# Schematic.net
KiCad netlist of a schematic drawn in Altium Designer
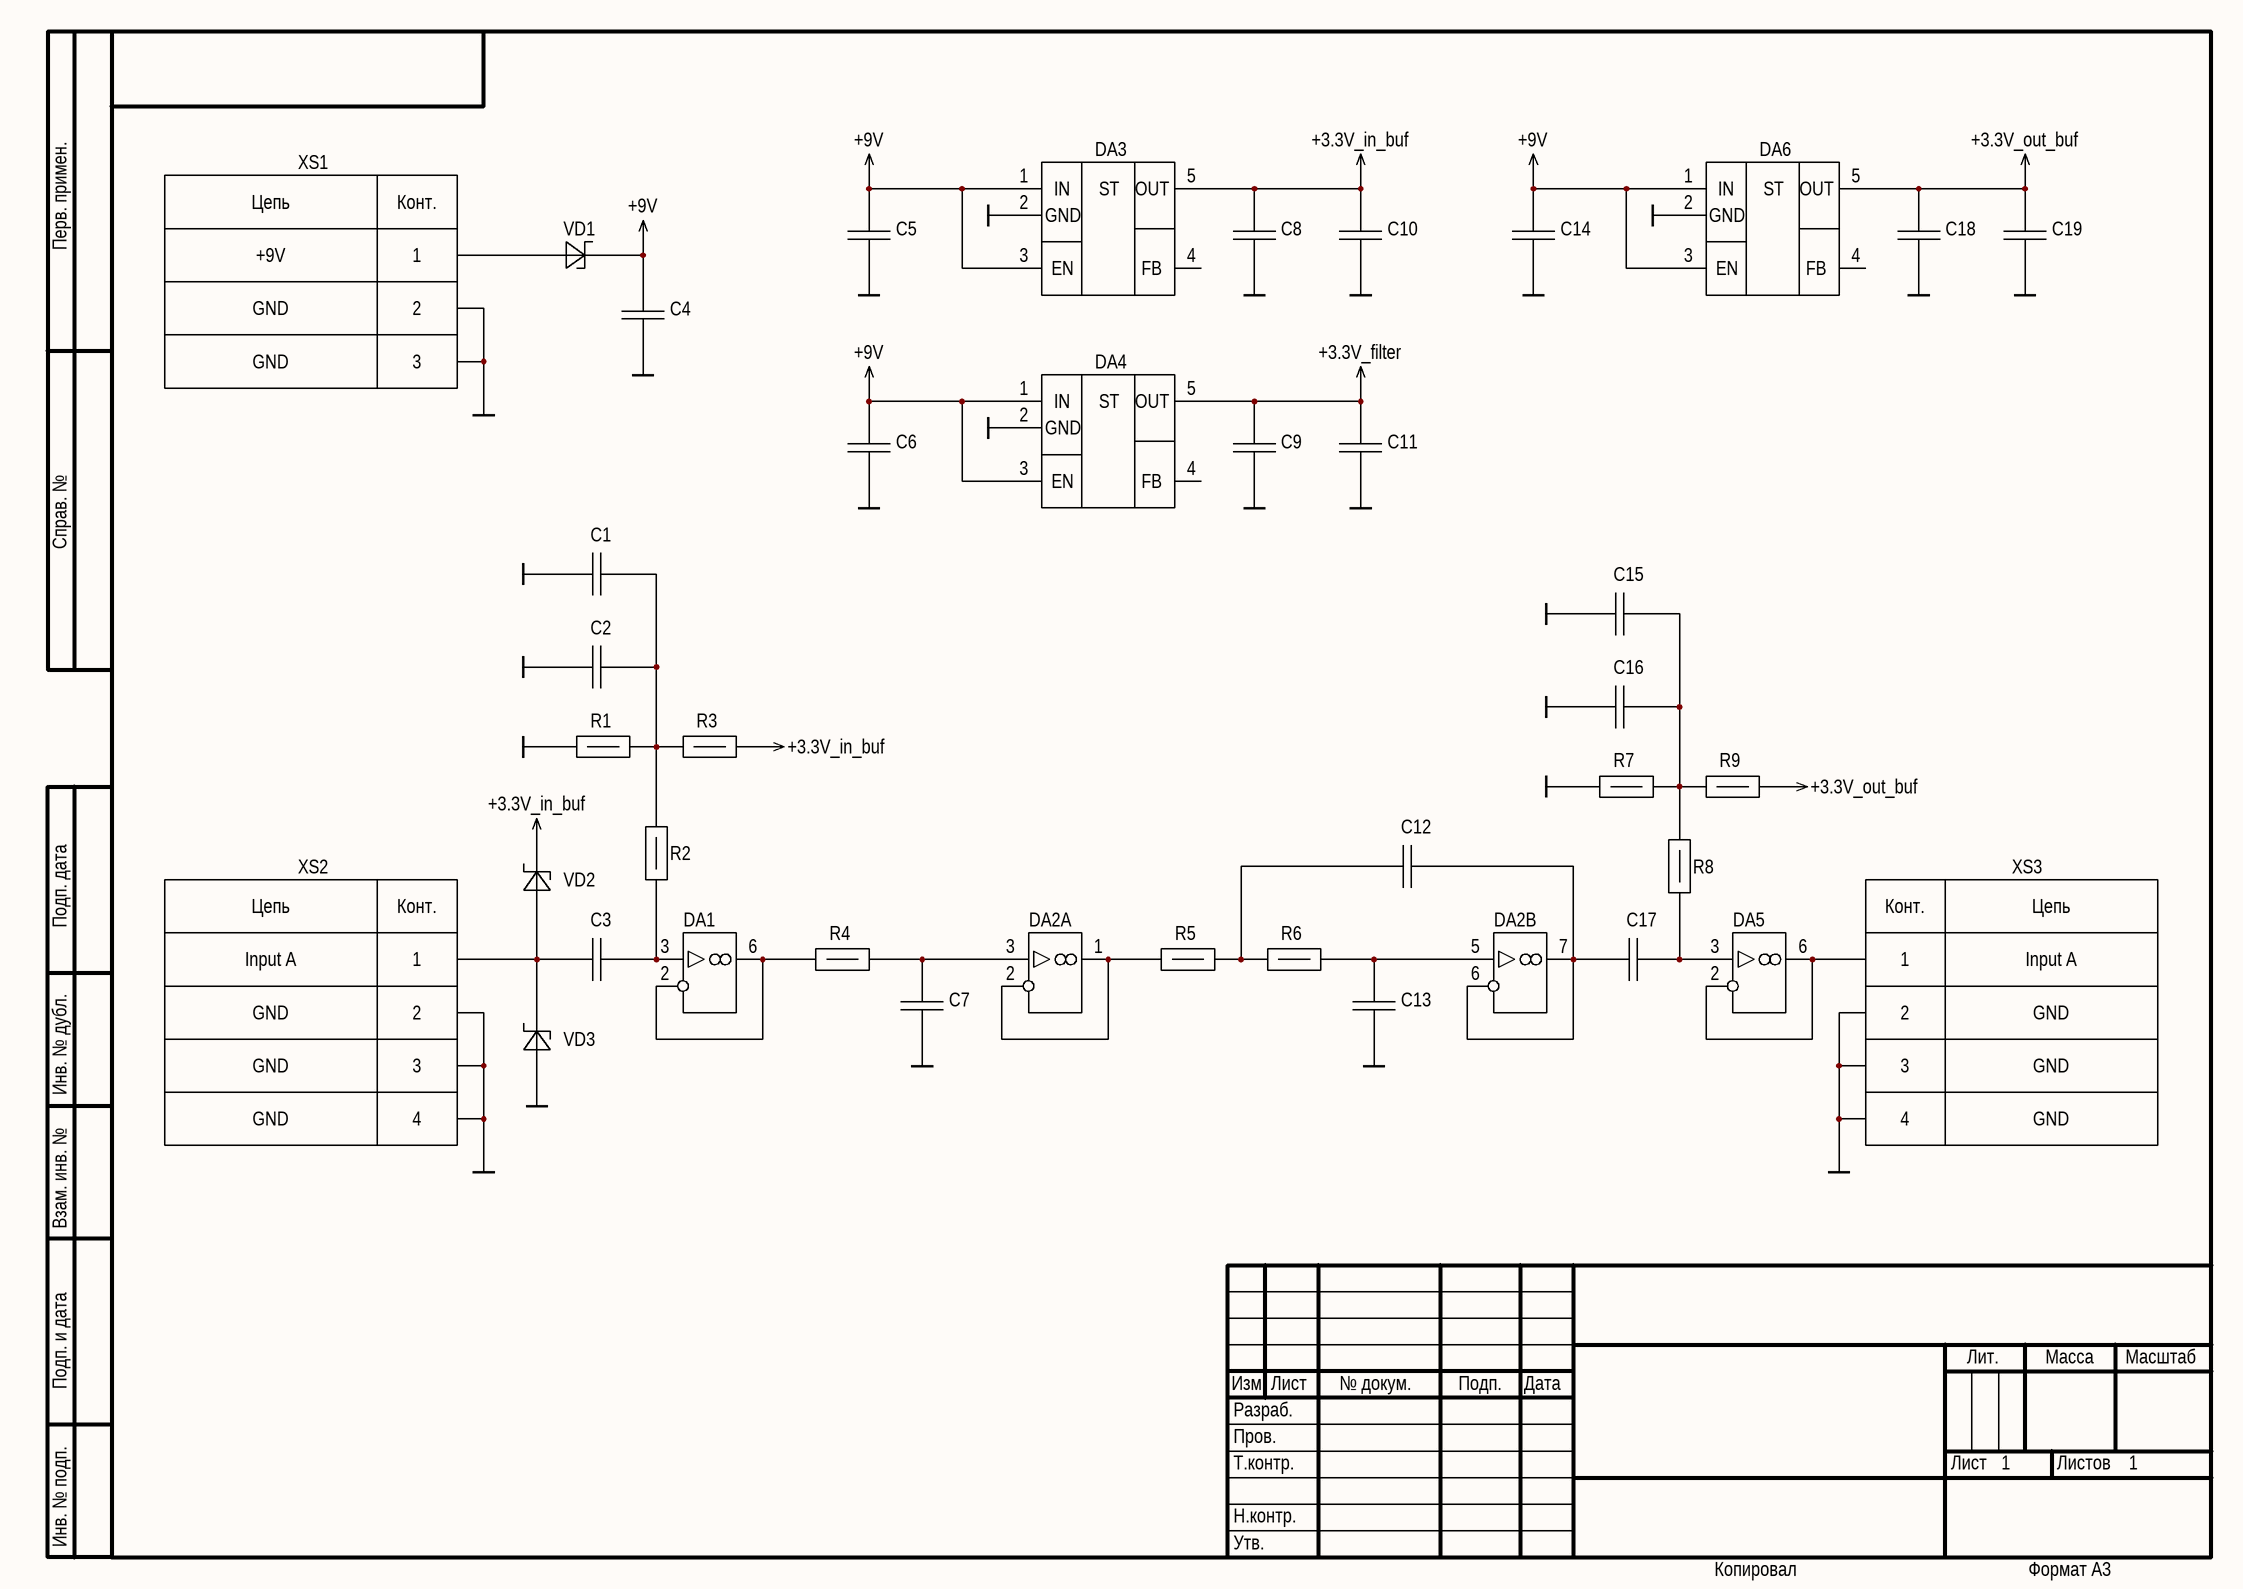
[diagram p0: Schematic.SchDoc]

(export (version "E")
  (design (tool "Eeschema 10.0.6"))
  (components
    (comp (ref "C1")
      (value "10 uF x 10 V")
      (footprint "CAPC2012X06N")
      (description "MLCC - Multilayer Ceramic Capacitors")
      (fields (field (name "TOLERANCE") "10%"))
      (libsource (lib "RLC") (part "KGM21AR71A106KU"))
    )
    (comp (ref "C2")
      (value "0.1 uF x 100 V")
      (footprint "CAPC2012X06N")
      (description "MLCC - Multilayer Ceramic Capacitors")
      (fields (field (name "TOLERANCE") "10%"))
      (libsource (lib "RLC") (part "C2012X7R2A104K125AE"))
    )
    (comp (ref "C3")
      (value "0.1 uF x 100 V")
      (footprint "CAPC2012X06N")
      (description "MLCC - Multilayer Ceramic Capacitors")
      (fields (field (name "TOLERANCE") "10%"))
      (libsource (lib "RLC") (part "C2012X7R2A104K125AE"))
    )
    (comp (ref "C4")
      (value "10 uF x 10 V")
      (footprint "CAPC2012X06N")
      (description "MLCC - Multilayer Ceramic Capacitors")
      (fields (field (name "TOLERANCE") "10%"))
      (libsource (lib "RLC") (part "KGM21AR71A106KU"))
    )
    (comp (ref "C5")
      (value "10 uF x 10 V")
      (footprint "CAPC2012X06N")
      (description "MLCC - Multilayer Ceramic Capacitors")
      (fields (field (name "TOLERANCE") "10%"))
      (libsource (lib "RLC") (part "KGM21AR71A106KU"))
    )
    (comp (ref "C6")
      (value "10 uF x 10 V")
      (footprint "CAPC2012X06N")
      (description "MLCC - Multilayer Ceramic Capacitors")
      (fields (field (name "TOLERANCE") "10%"))
      (libsource (lib "RLC") (part "KGM21AR71A106KU"))
    )
    (comp (ref "C7")
      (value "1 nF x 450 V")
      (footprint "CAPC2012X06N")
      (description "MLCC - Multilayer Ceramic Capacitors")
      (fields (field (name "TOLERANCE") "5%"))
      (libsource (lib "RLC") (part "C2012NP02W102J060AA"))
    )
    (comp (ref "C8")
      (value "0.1 uF x 100 V")
      (footprint "CAPC2012X06N")
      (description "MLCC - Multilayer Ceramic Capacitors")
      (fields (field (name "TOLERANCE") "10%"))
      (libsource (lib "RLC") (part "C2012X7R2A104K125AE"))
    )
    (comp (ref "C9")
      (value "0.1 uF x 100 V")
      (footprint "CAPC2012X06N")
      (description "MLCC - Multilayer Ceramic Capacitors")
      (fields (field (name "TOLERANCE") "10%"))
      (libsource (lib "RLC") (part "C2012X7R2A104K125AE"))
    )
    (comp (ref "C10")
      (value "10 uF x 10 V")
      (footprint "CAPC2012X06N")
      (description "MLCC - Multilayer Ceramic Capacitors")
      (fields (field (name "TOLERANCE") "10%"))
      (libsource (lib "RLC") (part "KGM21AR71A106KU"))
    )
    (comp (ref "C11")
      (value "10 uF x 10 V")
      (footprint "CAPC2012X06N")
      (description "MLCC - Multilayer Ceramic Capacitors")
      (fields (field (name "TOLERANCE") "10%"))
      (libsource (lib "RLC") (part "KGM21AR71A106KU"))
    )
    (comp (ref "C12")
      (value "2 nF x 25 V")
      (footprint "CAPC2012X06N")
      (description "MLCC - Multilayer Ceramic Capacitors")
      (fields (field (name "TOLERANCE") "5%"))
      (libsource (lib "RLC") (part "08053A202JAT2A"))
    )
    (comp (ref "C13")
      (value "1 nF x 450 V")
      (footprint "CAPC2012X06N")
      (description "MLCC - Multilayer Ceramic Capacitors")
      (fields (field (name "TOLERANCE") "5%"))
      (libsource (lib "RLC") (part "C2012NP02W102J060AA"))
    )
    (comp (ref "C14")
      (value "10 uF x 10 V")
      (footprint "CAPC2012X06N")
      (description "MLCC - Multilayer Ceramic Capacitors")
      (fields (field (name "TOLERANCE") "10%"))
      (libsource (lib "RLC") (part "KGM21AR71A106KU"))
    )
    (comp (ref "C15")
      (value "10 uF x 10 V")
      (footprint "CAPC2012X06N")
      (description "MLCC - Multilayer Ceramic Capacitors")
      (fields (field (name "TOLERANCE") "10%"))
      (libsource (lib "RLC") (part "KGM21AR71A106KU"))
    )
    (comp (ref "C16")
      (value "0.1 uF x 100 V")
      (footprint "CAPC2012X06N")
      (description "MLCC - Multilayer Ceramic Capacitors")
      (fields (field (name "TOLERANCE") "10%"))
      (libsource (lib "RLC") (part "C2012X7R2A104K125AE"))
    )
    (comp (ref "C17")
      (value "0.1 uF x 100 V")
      (footprint "CAPC2012X06N")
      (description "MLCC - Multilayer Ceramic Capacitors")
      (fields (field (name "TOLERANCE") "10%"))
      (libsource (lib "RLC") (part "C2012X7R2A104K125AE"))
    )
    (comp (ref "C18")
      (value "0.1 uF x 100 V")
      (footprint "CAPC2012X06N")
      (description "MLCC - Multilayer Ceramic Capacitors")
      (fields (field (name "TOLERANCE") "10%"))
      (libsource (lib "RLC") (part "C2012X7R2A104K125AE"))
    )
    (comp (ref "C19")
      (value "10 uF x 10 V")
      (footprint "CAPC2012X06N")
      (description "MLCC - Multilayer Ceramic Capacitors")
      (fields (field (name "TOLERANCE") "10%"))
      (libsource (lib "RLC") (part "KGM21AR71A106KU"))
    )
    (comp (ref "DA1")
      (value "OPA735AID")
      (footprint "D0008A")
      (description "0.05µV/°C max, SINGLE-SUPPLY CMOS OPERATIONAL AMPLIFIERS Zer∅-Drift Series")
      (libsource (lib "OPAx73x") (part "OPA735AID"))
    )
    (comp (ref "DA2")
      (value "OPA2735AIDGKR")
      (footprint "DGK0008A")
      (description "0.05µV/°C max, SINGLE-SUPPLY CMOS OPERATIONAL AMPLIFIERS Zer∅-Drift Series")
      (libsource (lib "OPAx73x") (part "OPA2735AIDGKR"))
    )
    (comp (ref "DA3")
      (value "TPS76333DBVT")
      (footprint "DBV0005A")
      (description "150mA, 10V, Low-Dropout Voltage Regulator")
      (libsource (lib "TPS763") (part "TPS76333DBVT"))
    )
    (comp (ref "DA4")
      (value "TPS76333DBVT")
      (footprint "DBV0005A")
      (description "150mA, 10V, Low-Dropout Voltage Regulator")
      (libsource (lib "TPS763") (part "TPS76333DBVT"))
    )
    (comp (ref "DA5")
      (value "OPA735AID")
      (footprint "D0008A")
      (description "0.05µV/°C max, SINGLE-SUPPLY CMOS OPERATIONAL AMPLIFIERS Zer∅-Drift Series")
      (libsource (lib "OPAx73x") (part "OPA735AID"))
    )
    (comp (ref "DA6")
      (value "TPS76333DBVT")
      (footprint "DBV0005A")
      (description "150mA, 10V, Low-Dropout Voltage Regulator")
      (libsource (lib "TPS763") (part "TPS76333DBVT"))
    )
    (comp (ref "R1")
      (value "100 kOhms")
      (footprint "RESC2012X06N")
      (description "Thick Film Chip Resistors")
      (fields (field (name "TOLERANCE") "5%"))
      (libsource (lib "RLC") (part "ERJ-HP6J104V"))
    )
    (comp (ref "R2")
      (value "100 kOhms")
      (footprint "RESC2012X06N")
      (description "Thick Film Chip Resistors")
      (fields (field (name "TOLERANCE") "5%"))
      (libsource (lib "RLC") (part "ERJ-HP6J104V"))
    )
    (comp (ref "R3")
      (value "100 kOhms")
      (footprint "RESC2012X06N")
      (description "Thick Film Chip Resistors")
      (fields (field (name "TOLERANCE") "5%"))
      (libsource (lib "RLC") (part "ERJ-HP6J104V"))
    )
    (comp (ref "R4")
      (value "8.06 kOhms")
      (footprint "RESC2012X06N")
      (description "Thick Film Chip Resistors")
      (fields (field (name "TOLERANCE") "1%"))
      (libsource (lib "RLC") (part "ERJ-P06F8061V"))
    )
    (comp (ref "R5")
      (value "4.42 kOhms")
      (footprint "RESC2012X06N")
      (description "Thick Film Chip Resistors")
      (fields (field (name "TOLERANCE") "0.5%"))
      (libsource (lib "RLC") (part "ERJ-6RBD4421V"))
    )
    (comp (ref "R6")
      (value "6.19 kOhms")
      (footprint "RESC2012X06N")
      (description "Thick Film Chip Resistors")
      (fields (field (name "TOLERANCE") "1%"))
      (libsource (lib "RLC") (part "ERJ-HP6F6191V"))
    )
    (comp (ref "R7")
      (value "100 kOhms")
      (footprint "RESC2012X06N")
      (description "Thick Film Chip Resistors")
      (fields (field (name "TOLERANCE") "5%"))
      (libsource (lib "RLC") (part "ERJ-HP6J104V"))
    )
    (comp (ref "R8")
      (value "100 kOhms")
      (footprint "RESC2012X06N")
      (description "Thick Film Chip Resistors")
      (fields (field (name "TOLERANCE") "5%"))
      (libsource (lib "RLC") (part "ERJ-HP6J104V"))
    )
    (comp (ref "R9")
      (value "100 kOhms")
      (footprint "RESC2012X06N")
      (description "Thick Film Chip Resistors")
      (fields (field (name "TOLERANCE") "5%"))
      (libsource (lib "RLC") (part "ERJ-HP6J104V"))
    )
    (comp (ref "VD1")
      (value "BAT54W-HG3-18")
      (footprint "SOD-123")
      (description "Schottky Diodes & Rectifiers 30V Schottky DIODE")
      (libsource (lib "BAT54W-HG3-18") (part "BAT54W-HG3-18"))
    )
    (comp (ref "VD2")
      (value "BAT54W-HG3-18")
      (footprint "SOD-123")
      (description "Schottky Diodes & Rectifiers 30V Schottky DIODE")
      (libsource (lib "BAT54W-HG3-18") (part "BAT54W-HG3-18"))
    )
    (comp (ref "VD3")
      (value "BAT54W-HG3-18")
      (footprint "SOD-123")
      (description "Schottky Diodes & Rectifiers 30V Schottky DIODE")
      (libsource (lib "BAT54W-HG3-18") (part "BAT54W-HG3-18"))
    )
    (comp (ref "XS1")
      (value "PJ-002AH")
      (footprint "PJ-002AH (Same Sky)")
      (description "DC POWER JACK")
      (libsource (lib "PJ-002AH") (part "PJ-002AH"))
    )
    (comp (ref "XS2")
      (value "0731385003")
      (footprint "0731385003 (Molex)")
      (description "BNC Connector Jack")
      (libsource (lib "0731385003") (part "0731385003"))
    )
    (comp (ref "XS3")
      (value "0731385003")
      (footprint "0731385003 (Molex)")
      (description "BNC Connector Jack")
      (libsource (lib "0731385003") (part "0731385003"))
    )
  )
  (nets
    (net (code "1") (name "+3.3V_filter") (class "Default")
      (node (ref "C11") (pin "1") (pinfunction "1_1") (pintype "passive"))
      (node (ref "C9") (pin "1") (pinfunction "1_1") (pintype "passive"))
      (node (ref "DA4") (pin "5") (pinfunction "OUT_5") (pintype "passive"))
    )
    (net (code "2") (name "+3.3V_in_buf") (class "Default")
      (node (ref "C10") (pin "1") (pinfunction "1_1") (pintype "passive"))
      (node (ref "C8") (pin "1") (pinfunction "1_1") (pintype "passive"))
      (node (ref "DA3") (pin "5") (pinfunction "OUT_5") (pintype "passive"))
      (node (ref "R3") (pin "1") (pinfunction "1_1") (pintype "passive"))
      (node (ref "VD2") (pin "1") (pinfunction "1_1") (pintype "passive"))
    )
    (net (code "3") (name "+3.3V_out_buf") (class "Default")
      (node (ref "C18") (pin "1") (pinfunction "1_1") (pintype "passive"))
      (node (ref "C19") (pin "1") (pinfunction "1_1") (pintype "passive"))
      (node (ref "DA6") (pin "5") (pinfunction "OUT_5") (pintype "passive"))
      (node (ref "R9") (pin "1") (pinfunction "1_1") (pintype "passive"))
    )
    (net (code "4") (name "+9V") (class "Default")
      (node (ref "C14") (pin "1") (pinfunction "1_1") (pintype "passive"))
      (node (ref "C4") (pin "1") (pinfunction "1_1") (pintype "passive"))
      (node (ref "C5") (pin "1") (pinfunction "1_1") (pintype "passive"))
      (node (ref "C6") (pin "1") (pinfunction "1_1") (pintype "passive"))
      (node (ref "DA3") (pin "1") (pinfunction "IN_1") (pintype "passive"))
      (node (ref "DA3") (pin "3") (pinfunction "EN_3") (pintype "passive"))
      (node (ref "DA4") (pin "1") (pinfunction "IN_1") (pintype "passive"))
      (node (ref "DA4") (pin "3") (pinfunction "EN_3") (pintype "passive"))
      (node (ref "DA6") (pin "1") (pinfunction "IN_1") (pintype "passive"))
      (node (ref "DA6") (pin "3") (pinfunction "EN_3") (pintype "passive"))
      (node (ref "VD1") (pin "1") (pinfunction "1_1") (pintype "passive"))
    )
    (net (code "5") (name "GND") (class "Default")
      (node (ref "C1") (pin "1") (pinfunction "1_1") (pintype "passive"))
      (node (ref "C10") (pin "2") (pinfunction "2_2") (pintype "passive"))
      (node (ref "C11") (pin "2") (pinfunction "2_2") (pintype "passive"))
      (node (ref "C13") (pin "2") (pinfunction "2_2") (pintype "passive"))
      (node (ref "C14") (pin "2") (pinfunction "2_2") (pintype "passive"))
      (node (ref "C15") (pin "1") (pinfunction "1_1") (pintype "passive"))
      (node (ref "C16") (pin "2") (pinfunction "2_2") (pintype "passive"))
      (node (ref "C18") (pin "2") (pinfunction "2_2") (pintype "passive"))
      (node (ref "C19") (pin "2") (pinfunction "2_2") (pintype "passive"))
      (node (ref "C2") (pin "2") (pinfunction "2_2") (pintype "passive"))
      (node (ref "C4") (pin "2") (pinfunction "2_2") (pintype "passive"))
      (node (ref "C5") (pin "2") (pinfunction "2_2") (pintype "passive"))
      (node (ref "C6") (pin "2") (pinfunction "2_2") (pintype "passive"))
      (node (ref "C7") (pin "2") (pinfunction "2_2") (pintype "passive"))
      (node (ref "C8") (pin "2") (pinfunction "2_2") (pintype "passive"))
      (node (ref "C9") (pin "2") (pinfunction "2_2") (pintype "passive"))
      (node (ref "DA3") (pin "2") (pinfunction "GND_2") (pintype "passive"))
      (node (ref "DA4") (pin "2") (pinfunction "GND_2") (pintype "passive"))
      (node (ref "DA6") (pin "2") (pinfunction "GND_2") (pintype "passive"))
      (node (ref "R1") (pin "2") (pinfunction "2_2") (pintype "passive"))
      (node (ref "R7") (pin "2") (pinfunction "2_2") (pintype "passive"))
      (node (ref "VD3") (pin "2") (pinfunction "2_2") (pintype "passive"))
      (node (ref "XS1") (pin "2") (pinfunction "GND_2") (pintype "passive"))
      (node (ref "XS1") (pin "3") (pinfunction "GND_3") (pintype "passive"))
      (node (ref "XS2") (pin "2") (pinfunction "GND_2") (pintype "passive"))
      (node (ref "XS2") (pin "3") (pinfunction "GND_3") (pintype "passive"))
      (node (ref "XS2") (pin "4") (pinfunction "GND_4") (pintype "passive"))
      (node (ref "XS3") (pin "2") (pinfunction "GND_2") (pintype "passive"))
      (node (ref "XS3") (pin "3") (pinfunction "GND_3") (pintype "passive"))
      (node (ref "XS3") (pin "4") (pinfunction "GND_4") (pintype "passive"))
    )
    (net (code "6") (name "Net-(C1-Pad2)") (class "Default")
      (node (ref "C1") (pin "2") (pinfunction "2_2") (pintype "passive"))
      (node (ref "C2") (pin "1") (pinfunction "1_1") (pintype "passive"))
      (node (ref "R1") (pin "1") (pinfunction "1_1") (pintype "passive"))
      (node (ref "R2") (pin "2") (pinfunction "2_2") (pintype "passive"))
      (node (ref "R3") (pin "2") (pinfunction "2_2") (pintype "passive"))
    )
    (net (code "7") (name "Net-(C12-Pad1)") (class "Default")
      (node (ref "C12") (pin "1") (pinfunction "1_1") (pintype "passive"))
      (node (ref "R5") (pin "2") (pinfunction "2_2") (pintype "passive"))
      (node (ref "R6") (pin "1") (pinfunction "1_1") (pintype "passive"))
    )
    (net (code "8") (name "Net-(C15-Pad2)") (class "Default")
      (node (ref "C15") (pin "2") (pinfunction "2_2") (pintype "passive"))
      (node (ref "C16") (pin "1") (pinfunction "1_1") (pintype "passive"))
      (node (ref "R7") (pin "1") (pinfunction "1_1") (pintype "passive"))
      (node (ref "R8") (pin "2") (pinfunction "2_2") (pintype "passive"))
      (node (ref "R9") (pin "2") (pinfunction "2_2") (pintype "passive"))
    )
    (net (code "9") (name "Net-(DA1-+IN)") (class "Default")
      (node (ref "C3") (pin "1") (pinfunction "1_1") (pintype "passive"))
      (node (ref "DA1") (pin "3") (pinfunction "+IN_3") (pintype "passive"))
      (node (ref "R2") (pin "1") (pinfunction "1_1") (pintype "passive"))
    )
    (net (code "10") (name "Net-(DA1--IN)") (class "Default")
      (node (ref "DA1") (pin "2") (pinfunction "-IN_2") (pintype "passive"))
      (node (ref "DA1") (pin "6") (pinfunction "OUT_6") (pintype "passive"))
      (node (ref "R4") (pin "1") (pinfunction "1_1") (pintype "passive"))
    )
    (net (code "11") (name "Net-(DA2A-+IN_A)") (class "Default")
      (node (ref "C7") (pin "1") (pinfunction "1_1") (pintype "passive"))
      (node (ref "DA2") (pin "3") (pinfunction "+IN_A_3") (pintype "passive"))
      (node (ref "R4") (pin "2") (pinfunction "2_2") (pintype "passive"))
    )
    (net (code "12") (name "Net-(DA2A--IN_A)") (class "Default")
      (node (ref "DA2") (pin "1") (pinfunction "OUT_A_1") (pintype "passive"))
      (node (ref "DA2") (pin "2") (pinfunction "-IN_A_2") (pintype "passive"))
      (node (ref "R5") (pin "1") (pinfunction "1_1") (pintype "passive"))
    )
    (net (code "13") (name "Net-(DA2B-+IN_B)") (class "Default")
      (node (ref "C13") (pin "1") (pinfunction "1_1") (pintype "passive"))
      (node (ref "DA2") (pin "5") (pinfunction "+IN_B_5") (pintype "passive"))
      (node (ref "R6") (pin "2") (pinfunction "2_2") (pintype "passive"))
    )
    (net (code "14") (name "Net-(DA2B--IN_B)") (class "Default")
      (node (ref "C12") (pin "2") (pinfunction "2_2") (pintype "passive"))
      (node (ref "C17") (pin "2") (pinfunction "2_2") (pintype "passive"))
      (node (ref "DA2") (pin "6") (pinfunction "-IN_B_6") (pintype "passive"))
      (node (ref "DA2") (pin "7") (pinfunction "OUT_B_7") (pintype "passive"))
    )
    (net (code "15") (name "Net-(DA5-+IN)") (class "Default")
      (node (ref "C17") (pin "1") (pinfunction "1_1") (pintype "passive"))
      (node (ref "DA5") (pin "3") (pinfunction "+IN_3") (pintype "passive"))
      (node (ref "R8") (pin "1") (pinfunction "1_1") (pintype "passive"))
    )
    (net (code "16") (name "Net-(DA5--IN)") (class "Default")
      (node (ref "DA5") (pin "2") (pinfunction "-IN_2") (pintype "passive"))
      (node (ref "DA5") (pin "6") (pinfunction "OUT_6") (pintype "passive"))
      (node (ref "XS3") (pin "1") (pinfunction "Input_A_1") (pintype "passive"))
    )
    (net (code "17") (name "Net-(XS1-+9V)") (class "Default")
      (node (ref "VD1") (pin "2") (pinfunction "2_2") (pintype "passive"))
      (node (ref "XS1") (pin "1") (pinfunction "+9V_1") (pintype "passive"))
    )
    (net (code "18") (name "Net-(XS2-Input_A)") (class "Default")
      (node (ref "C3") (pin "2") (pinfunction "2_2") (pintype "passive"))
      (node (ref "VD2") (pin "2") (pinfunction "2_2") (pintype "passive"))
      (node (ref "VD3") (pin "1") (pinfunction "1_1") (pintype "passive"))
      (node (ref "XS2") (pin "1") (pinfunction "Input_A_1") (pintype "passive"))
    )
    (net (code "19") (name "unconnected-(DA3-FB-Pad4)") (class "Default")
      (node (ref "DA3") (pin "4") (pinfunction "FB_4") (pintype "passive"))
    )
    (net (code "20") (name "unconnected-(DA4-FB-Pad4)") (class "Default")
      (node (ref "DA4") (pin "4") (pinfunction "FB_4") (pintype "passive"))
    )
    (net (code "21") (name "unconnected-(DA6-FB-Pad4)") (class "Default")
      (node (ref "DA6") (pin "4") (pinfunction "FB_4") (pintype "passive"))
    )
  )
)
